# big7segment.net
KiCad netlist of a schematic drawn in EAGLE
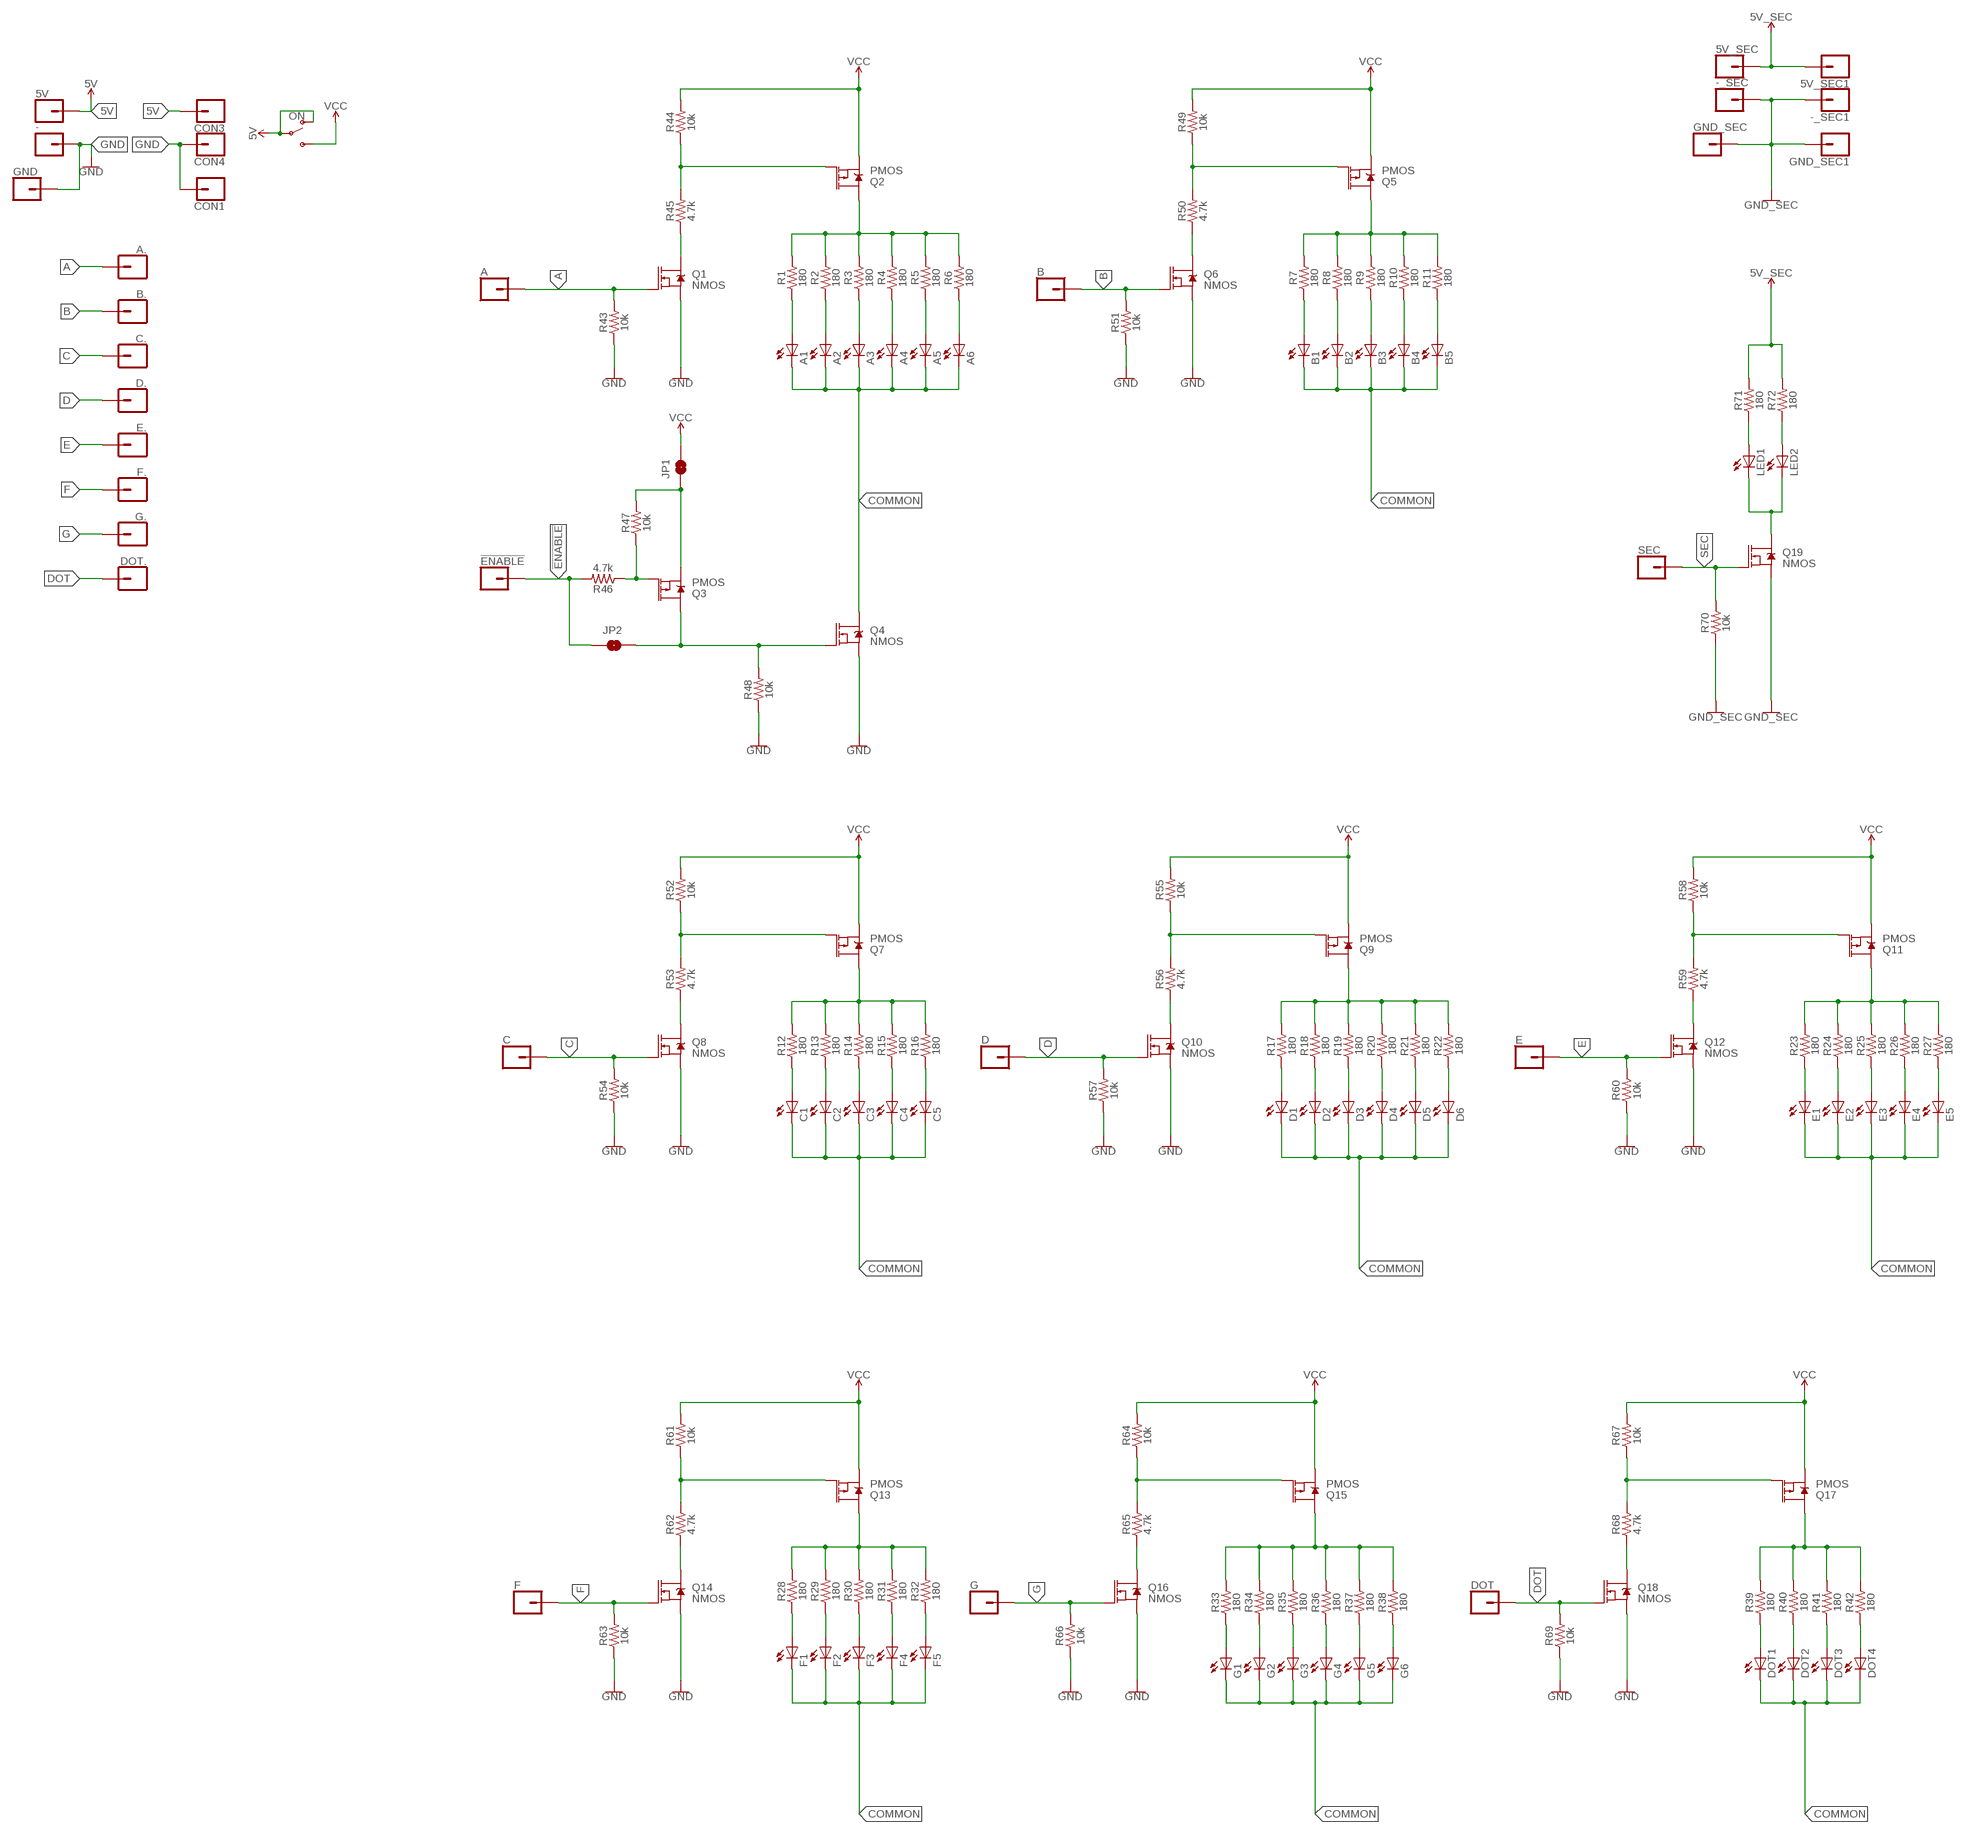
[diagram p0: schematic, sheet 1]

(export (version "E")
  (design (tool "Eeschema 10.0.6"))
  (components
    (comp (ref "!ENABLE!")
      (value "CONN_01OFFSET")
      (footprint "eagle-import:1X01_OFFSET")
      (libsource (lib "eagle-import") (part "CONN_01OFFSET"))
    )
    (comp (ref "-")
      (value "CONN_01OFFSET")
      (footprint "eagle-import:1X01_OFFSET")
      (libsource (lib "eagle-import") (part "CONN_01OFFSET"))
    )
    (comp (ref "-_SEC")
      (value "CONN_01OFFSET")
      (footprint "eagle-import:1X01_OFFSET")
      (libsource (lib "eagle-import") (part "CONN_01OFFSET"))
    )
    (comp (ref "-_SEC1")
      (value "CONN_01OFFSET")
      (footprint "eagle-import:1X01_OFFSET")
      (libsource (lib "eagle-import") (part "CONN_01OFFSET"))
    )
    (comp (ref "5V")
      (value "CONN_01OFFSET")
      (footprint "eagle-import:1X01_OFFSET")
      (libsource (lib "eagle-import") (part "CONN_01OFFSET"))
    )
    (comp (ref "5V_SEC")
      (value "CONN_01OFFSET")
      (footprint "eagle-import:1X01_OFFSET")
      (libsource (lib "eagle-import") (part "CONN_01OFFSET"))
    )
    (comp (ref "5V_SEC1")
      (value "CONN_01OFFSET")
      (footprint "eagle-import:1X01_OFFSET")
      (libsource (lib "eagle-import") (part "CONN_01OFFSET"))
    )
    (comp (ref "A")
      (value "CONN_01OFFSET")
      (footprint "eagle-import:1X01_OFFSET")
      (libsource (lib "eagle-import") (part "CONN_01OFFSET"))
    )
    (comp (ref "A.")
      (value "CONN_01OFFSET")
      (footprint "eagle-import:1X01_OFFSET")
      (libsource (lib "eagle-import") (part "CONN_01OFFSET"))
    )
    (comp (ref "A1")
      (value "LEDSML0805")
      (footprint "eagle-import:SML0805")
      (libsource (lib "eagle-import") (part "LEDSML0805"))
    )
    (comp (ref "A2")
      (value "LEDSML0805")
      (footprint "eagle-import:SML0805")
      (libsource (lib "eagle-import") (part "LEDSML0805"))
    )
    (comp (ref "A3")
      (value "LEDSML0805")
      (footprint "eagle-import:SML0805")
      (libsource (lib "eagle-import") (part "LEDSML0805"))
    )
    (comp (ref "A4")
      (value "LEDSML0805")
      (footprint "eagle-import:SML0805")
      (libsource (lib "eagle-import") (part "LEDSML0805"))
    )
    (comp (ref "A5")
      (value "LEDSML0805")
      (footprint "eagle-import:SML0805")
      (libsource (lib "eagle-import") (part "LEDSML0805"))
    )
    (comp (ref "A6")
      (value "LEDSML0805")
      (footprint "eagle-import:SML0805")
      (libsource (lib "eagle-import") (part "LEDSML0805"))
    )
    (comp (ref "B")
      (value "CONN_01OFFSET")
      (footprint "eagle-import:1X01_OFFSET")
      (libsource (lib "eagle-import") (part "CONN_01OFFSET"))
    )
    (comp (ref "B.")
      (value "CONN_01OFFSET")
      (footprint "eagle-import:1X01_OFFSET")
      (libsource (lib "eagle-import") (part "CONN_01OFFSET"))
    )
    (comp (ref "B1")
      (value "LEDSML0805")
      (footprint "eagle-import:SML0805")
      (libsource (lib "eagle-import") (part "LEDSML0805"))
    )
    (comp (ref "B2")
      (value "LEDSML0805")
      (footprint "eagle-import:SML0805")
      (libsource (lib "eagle-import") (part "LEDSML0805"))
    )
    (comp (ref "B3")
      (value "LEDSML0805")
      (footprint "eagle-import:SML0805")
      (libsource (lib "eagle-import") (part "LEDSML0805"))
    )
    (comp (ref "B4")
      (value "LEDSML0805")
      (footprint "eagle-import:SML0805")
      (libsource (lib "eagle-import") (part "LEDSML0805"))
    )
    (comp (ref "B5")
      (value "LEDSML0805")
      (footprint "eagle-import:SML0805")
      (libsource (lib "eagle-import") (part "LEDSML0805"))
    )
    (comp (ref "C")
      (value "CONN_01OFFSET")
      (footprint "eagle-import:1X01_OFFSET")
      (libsource (lib "eagle-import") (part "CONN_01OFFSET"))
    )
    (comp (ref "C.")
      (value "CONN_01OFFSET")
      (footprint "eagle-import:1X01_OFFSET")
      (libsource (lib "eagle-import") (part "CONN_01OFFSET"))
    )
    (comp (ref "C1")
      (value "LEDSML0805")
      (footprint "eagle-import:SML0805")
      (libsource (lib "eagle-import") (part "LEDSML0805"))
    )
    (comp (ref "C2")
      (value "LEDSML0805")
      (footprint "eagle-import:SML0805")
      (libsource (lib "eagle-import") (part "LEDSML0805"))
    )
    (comp (ref "C3")
      (value "LEDSML0805")
      (footprint "eagle-import:SML0805")
      (libsource (lib "eagle-import") (part "LEDSML0805"))
    )
    (comp (ref "C4")
      (value "LEDSML0805")
      (footprint "eagle-import:SML0805")
      (libsource (lib "eagle-import") (part "LEDSML0805"))
    )
    (comp (ref "C5")
      (value "LEDSML0805")
      (footprint "eagle-import:SML0805")
      (libsource (lib "eagle-import") (part "LEDSML0805"))
    )
    (comp (ref "CON1")
      (value "CONN_01OFFSET")
      (footprint "eagle-import:1X01_OFFSET")
      (libsource (lib "eagle-import") (part "CONN_01OFFSET"))
    )
    (comp (ref "CON3")
      (value "CONN_01OFFSET")
      (footprint "eagle-import:1X01_OFFSET")
      (libsource (lib "eagle-import") (part "CONN_01OFFSET"))
    )
    (comp (ref "CON4")
      (value "CONN_01OFFSET")
      (footprint "eagle-import:1X01_OFFSET")
      (libsource (lib "eagle-import") (part "CONN_01OFFSET"))
    )
    (comp (ref "D")
      (value "CONN_01OFFSET")
      (footprint "eagle-import:1X01_OFFSET")
      (libsource (lib "eagle-import") (part "CONN_01OFFSET"))
    )
    (comp (ref "D.")
      (value "CONN_01OFFSET")
      (footprint "eagle-import:1X01_OFFSET")
      (libsource (lib "eagle-import") (part "CONN_01OFFSET"))
    )
    (comp (ref "D1")
      (value "LEDSML0805")
      (footprint "eagle-import:SML0805")
      (libsource (lib "eagle-import") (part "LEDSML0805"))
    )
    (comp (ref "D2")
      (value "LEDSML0805")
      (footprint "eagle-import:SML0805")
      (libsource (lib "eagle-import") (part "LEDSML0805"))
    )
    (comp (ref "D3")
      (value "LEDSML0805")
      (footprint "eagle-import:SML0805")
      (libsource (lib "eagle-import") (part "LEDSML0805"))
    )
    (comp (ref "D4")
      (value "LEDSML0805")
      (footprint "eagle-import:SML0805")
      (libsource (lib "eagle-import") (part "LEDSML0805"))
    )
    (comp (ref "D5")
      (value "LEDSML0805")
      (footprint "eagle-import:SML0805")
      (libsource (lib "eagle-import") (part "LEDSML0805"))
    )
    (comp (ref "D6")
      (value "LEDSML0805")
      (footprint "eagle-import:SML0805")
      (libsource (lib "eagle-import") (part "LEDSML0805"))
    )
    (comp (ref "DOT")
      (value "CONN_01OFFSET")
      (footprint "eagle-import:1X01_OFFSET")
      (libsource (lib "eagle-import") (part "CONN_01OFFSET"))
    )
    (comp (ref "DOT.")
      (value "CONN_01OFFSET")
      (footprint "eagle-import:1X01_OFFSET")
      (libsource (lib "eagle-import") (part "CONN_01OFFSET"))
    )
    (comp (ref "DOT1")
      (value "LEDSML0805")
      (footprint "eagle-import:SML0805")
      (libsource (lib "eagle-import") (part "LEDSML0805"))
    )
    (comp (ref "DOT2")
      (value "LEDSML0805")
      (footprint "eagle-import:SML0805")
      (libsource (lib "eagle-import") (part "LEDSML0805"))
    )
    (comp (ref "DOT3")
      (value "LEDSML0805")
      (footprint "eagle-import:SML0805")
      (libsource (lib "eagle-import") (part "LEDSML0805"))
    )
    (comp (ref "DOT4")
      (value "LEDSML0805")
      (footprint "eagle-import:SML0805")
      (libsource (lib "eagle-import") (part "LEDSML0805"))
    )
    (comp (ref "E")
      (value "CONN_01OFFSET")
      (footprint "eagle-import:1X01_OFFSET")
      (libsource (lib "eagle-import") (part "CONN_01OFFSET"))
    )
    (comp (ref "E.")
      (value "CONN_01OFFSET")
      (footprint "eagle-import:1X01_OFFSET")
      (libsource (lib "eagle-import") (part "CONN_01OFFSET"))
    )
    (comp (ref "E1")
      (value "LEDSML0805")
      (footprint "eagle-import:SML0805")
      (libsource (lib "eagle-import") (part "LEDSML0805"))
    )
    (comp (ref "E2")
      (value "LEDSML0805")
      (footprint "eagle-import:SML0805")
      (libsource (lib "eagle-import") (part "LEDSML0805"))
    )
    (comp (ref "E3")
      (value "LEDSML0805")
      (footprint "eagle-import:SML0805")
      (libsource (lib "eagle-import") (part "LEDSML0805"))
    )
    (comp (ref "E4")
      (value "LEDSML0805")
      (footprint "eagle-import:SML0805")
      (libsource (lib "eagle-import") (part "LEDSML0805"))
    )
    (comp (ref "E5")
      (value "LEDSML0805")
      (footprint "eagle-import:SML0805")
      (libsource (lib "eagle-import") (part "LEDSML0805"))
    )
    (comp (ref "F")
      (value "CONN_01OFFSET")
      (footprint "eagle-import:1X01_OFFSET")
      (libsource (lib "eagle-import") (part "CONN_01OFFSET"))
    )
    (comp (ref "F.")
      (value "CONN_01OFFSET")
      (footprint "eagle-import:1X01_OFFSET")
      (libsource (lib "eagle-import") (part "CONN_01OFFSET"))
    )
    (comp (ref "F1")
      (value "LEDSML0805")
      (footprint "eagle-import:SML0805")
      (libsource (lib "eagle-import") (part "LEDSML0805"))
    )
    (comp (ref "F2")
      (value "LEDSML0805")
      (footprint "eagle-import:SML0805")
      (libsource (lib "eagle-import") (part "LEDSML0805"))
    )
    (comp (ref "F3")
      (value "LEDSML0805")
      (footprint "eagle-import:SML0805")
      (libsource (lib "eagle-import") (part "LEDSML0805"))
    )
    (comp (ref "F4")
      (value "LEDSML0805")
      (footprint "eagle-import:SML0805")
      (libsource (lib "eagle-import") (part "LEDSML0805"))
    )
    (comp (ref "F5")
      (value "LEDSML0805")
      (footprint "eagle-import:SML0805")
      (libsource (lib "eagle-import") (part "LEDSML0805"))
    )
    (comp (ref "G")
      (value "CONN_01OFFSET")
      (footprint "eagle-import:1X01_OFFSET")
      (libsource (lib "eagle-import") (part "CONN_01OFFSET"))
    )
    (comp (ref "G.")
      (value "CONN_01OFFSET")
      (footprint "eagle-import:1X01_OFFSET")
      (libsource (lib "eagle-import") (part "CONN_01OFFSET"))
    )
    (comp (ref "G1")
      (value "LEDSML0805")
      (footprint "eagle-import:SML0805")
      (libsource (lib "eagle-import") (part "LEDSML0805"))
    )
    (comp (ref "G2")
      (value "LEDSML0805")
      (footprint "eagle-import:SML0805")
      (libsource (lib "eagle-import") (part "LEDSML0805"))
    )
    (comp (ref "G3")
      (value "LEDSML0805")
      (footprint "eagle-import:SML0805")
      (libsource (lib "eagle-import") (part "LEDSML0805"))
    )
    (comp (ref "G4")
      (value "LEDSML0805")
      (footprint "eagle-import:SML0805")
      (libsource (lib "eagle-import") (part "LEDSML0805"))
    )
    (comp (ref "G5")
      (value "LEDSML0805")
      (footprint "eagle-import:SML0805")
      (libsource (lib "eagle-import") (part "LEDSML0805"))
    )
    (comp (ref "G6")
      (value "LEDSML0805")
      (footprint "eagle-import:SML0805")
      (libsource (lib "eagle-import") (part "LEDSML0805"))
    )
    (comp (ref "GND")
      (value "CONN_01OFFSET")
      (footprint "eagle-import:1X01_OFFSET")
      (libsource (lib "eagle-import") (part "CONN_01OFFSET"))
    )
    (comp (ref "GND_SEC")
      (value "CONN_01OFFSET")
      (footprint "eagle-import:1X01_OFFSET")
      (libsource (lib "eagle-import") (part "CONN_01OFFSET"))
    )
    (comp (ref "GND_SEC1")
      (value "CONN_01OFFSET")
      (footprint "eagle-import:1X01_OFFSET")
      (libsource (lib "eagle-import") (part "CONN_01OFFSET"))
    )
    (comp (ref "JP1")
      (value "JUMPER-SMT_2_NC_TRACE_NO-SILK")
      (footprint "eagle-import:SMT-JUMPER_2_NC_TRACE_NO-SILK")
      (libsource (lib "eagle-import") (part "JUMPER-SMT_2_NC_TRACE_NO-SILK"))
    )
    (comp (ref "JP2")
      (value "JUMPER-SMT_2_NO_NO-SILK")
      (footprint "eagle-import:SMT-JUMPER_2_NO_NO-SILK")
      (libsource (lib "eagle-import") (part "JUMPER-SMT_2_NO_NO-SILK"))
    )
    (comp (ref "LED1")
      (value "LED5MM")
      (footprint "eagle-import:LED5MM")
      (libsource (lib "eagle-import") (part "LED5MM"))
    )
    (comp (ref "LED2")
      (value "LED5MM")
      (footprint "eagle-import:LED5MM")
      (libsource (lib "eagle-import") (part "LED5MM"))
    )
    (comp (ref "ON")
      (value "SWITCH-SPDT-PTH-11.6X4.0MM")
      (footprint "eagle-import:SWITCH_SPDT_PTH_11.6X4.0MM")
      (libsource (lib "eagle-import") (part "SWITCH-SPDT-PTH-11.6X4.0MM"))
    )
    (comp (ref "Q1")
      (value "NMOS")
      (footprint "eagle-import:SOT23-3")
      (libsource (lib "eagle-import") (part "MOSFET-NCH-AO3404A"))
    )
    (comp (ref "Q2")
      (value "PMOS")
      (footprint "eagle-import:SOT23-3")
      (libsource (lib "eagle-import") (part "MOSFET_PCH-DMG2307L"))
    )
    (comp (ref "Q3")
      (value "PMOS")
      (footprint "eagle-import:SOT23-3")
      (libsource (lib "eagle-import") (part "MOSFET_PCH-DMG2307L"))
    )
    (comp (ref "Q4")
      (value "NMOS")
      (footprint "eagle-import:SOT23-3")
      (libsource (lib "eagle-import") (part "MOSFET-NCH-AO3404A"))
    )
    (comp (ref "Q5")
      (value "PMOS")
      (footprint "eagle-import:SOT23-3")
      (libsource (lib "eagle-import") (part "MOSFET_PCH-DMG2307L"))
    )
    (comp (ref "Q6")
      (value "NMOS")
      (footprint "eagle-import:SOT23-3")
      (libsource (lib "eagle-import") (part "MOSFET-NCH-AO3404A"))
    )
    (comp (ref "Q7")
      (value "PMOS")
      (footprint "eagle-import:SOT23-3")
      (libsource (lib "eagle-import") (part "MOSFET_PCH-DMG2307L"))
    )
    (comp (ref "Q8")
      (value "NMOS")
      (footprint "eagle-import:SOT23-3")
      (libsource (lib "eagle-import") (part "MOSFET-NCH-AO3404A"))
    )
    (comp (ref "Q9")
      (value "PMOS")
      (footprint "eagle-import:SOT23-3")
      (libsource (lib "eagle-import") (part "MOSFET_PCH-DMG2307L"))
    )
    (comp (ref "Q10")
      (value "NMOS")
      (footprint "eagle-import:SOT23-3")
      (libsource (lib "eagle-import") (part "MOSFET-NCH-AO3404A"))
    )
    (comp (ref "Q11")
      (value "PMOS")
      (footprint "eagle-import:SOT23-3")
      (libsource (lib "eagle-import") (part "MOSFET_PCH-DMG2307L"))
    )
    (comp (ref "Q12")
      (value "NMOS")
      (footprint "eagle-import:SOT23-3")
      (libsource (lib "eagle-import") (part "MOSFET-NCH-AO3404A"))
    )
    (comp (ref "Q13")
      (value "PMOS")
      (footprint "eagle-import:SOT23-3")
      (libsource (lib "eagle-import") (part "MOSFET_PCH-DMG2307L"))
    )
    (comp (ref "Q14")
      (value "NMOS")
      (footprint "eagle-import:SOT23-3")
      (libsource (lib "eagle-import") (part "MOSFET-NCH-AO3404A"))
    )
    (comp (ref "Q15")
      (value "PMOS")
      (footprint "eagle-import:SOT23-3")
      (libsource (lib "eagle-import") (part "MOSFET_PCH-DMG2307L"))
    )
    (comp (ref "Q16")
      (value "NMOS")
      (footprint "eagle-import:SOT23-3")
      (libsource (lib "eagle-import") (part "MOSFET-NCH-AO3404A"))
    )
    (comp (ref "Q17")
      (value "PMOS")
      (footprint "eagle-import:SOT23-3")
      (libsource (lib "eagle-import") (part "MOSFET_PCH-DMG2307L"))
    )
    (comp (ref "Q18")
      (value "NMOS")
      (footprint "eagle-import:SOT23-3")
      (libsource (lib "eagle-import") (part "MOSFET-NCH-AO3404A"))
    )
    (comp (ref "Q19")
      (value "NMOS")
      (footprint "eagle-import:SOT23-3")
      (libsource (lib "eagle-import") (part "MOSFET-NCH-AO3404A"))
    )
    (comp (ref "R1")
      (value "180")
      (footprint "eagle-import:0805")
      (libsource (lib "eagle-import") (part "0.3OHM-0805-1/8W-1%"))
    )
    (comp (ref "R2")
      (value "180")
      (footprint "eagle-import:0805")
      (libsource (lib "eagle-import") (part "0.3OHM-0805-1/8W-1%"))
    )
    (comp (ref "R3")
      (value "180")
      (footprint "eagle-import:0805")
      (libsource (lib "eagle-import") (part "0.3OHM-0805-1/8W-1%"))
    )
    (comp (ref "R4")
      (value "180")
      (footprint "eagle-import:0805")
      (libsource (lib "eagle-import") (part "0.3OHM-0805-1/8W-1%"))
    )
    (comp (ref "R5")
      (value "180")
      (footprint "eagle-import:0805")
      (libsource (lib "eagle-import") (part "0.3OHM-0805-1/8W-1%"))
    )
    (comp (ref "R6")
      (value "180")
      (footprint "eagle-import:0805")
      (libsource (lib "eagle-import") (part "0.3OHM-0805-1/8W-1%"))
    )
    (comp (ref "R7")
      (value "180")
      (footprint "eagle-import:0805")
      (libsource (lib "eagle-import") (part "0.3OHM-0805-1/8W-1%"))
    )
    (comp (ref "R8")
      (value "180")
      (footprint "eagle-import:0805")
      (libsource (lib "eagle-import") (part "0.3OHM-0805-1/8W-1%"))
    )
    (comp (ref "R9")
      (value "180")
      (footprint "eagle-import:0805")
      (libsource (lib "eagle-import") (part "0.3OHM-0805-1/8W-1%"))
    )
    (comp (ref "R10")
      (value "180")
      (footprint "eagle-import:0805")
      (libsource (lib "eagle-import") (part "0.3OHM-0805-1/8W-1%"))
    )
    (comp (ref "R11")
      (value "180")
      (footprint "eagle-import:0805")
      (libsource (lib "eagle-import") (part "0.3OHM-0805-1/8W-1%"))
    )
    (comp (ref "R12")
      (value "180")
      (footprint "eagle-import:0805")
      (libsource (lib "eagle-import") (part "0.3OHM-0805-1/8W-1%"))
    )
    (comp (ref "R13")
      (value "180")
      (footprint "eagle-import:0805")
      (libsource (lib "eagle-import") (part "0.3OHM-0805-1/8W-1%"))
    )
    (comp (ref "R14")
      (value "180")
      (footprint "eagle-import:0805")
      (libsource (lib "eagle-import") (part "0.3OHM-0805-1/8W-1%"))
    )
    (comp (ref "R15")
      (value "180")
      (footprint "eagle-import:0805")
      (libsource (lib "eagle-import") (part "0.3OHM-0805-1/8W-1%"))
    )
    (comp (ref "R16")
      (value "180")
      (footprint "eagle-import:0805")
      (libsource (lib "eagle-import") (part "0.3OHM-0805-1/8W-1%"))
    )
    (comp (ref "R17")
      (value "180")
      (footprint "eagle-import:0805")
      (libsource (lib "eagle-import") (part "0.3OHM-0805-1/8W-1%"))
    )
    (comp (ref "R18")
      (value "180")
      (footprint "eagle-import:0805")
      (libsource (lib "eagle-import") (part "0.3OHM-0805-1/8W-1%"))
    )
    (comp (ref "R19")
      (value "180")
      (footprint "eagle-import:0805")
      (libsource (lib "eagle-import") (part "0.3OHM-0805-1/8W-1%"))
    )
    (comp (ref "R20")
      (value "180")
      (footprint "eagle-import:0805")
      (libsource (lib "eagle-import") (part "0.3OHM-0805-1/8W-1%"))
    )
    (comp (ref "R21")
      (value "180")
      (footprint "eagle-import:0805")
      (libsource (lib "eagle-import") (part "0.3OHM-0805-1/8W-1%"))
    )
    (comp (ref "R22")
      (value "180")
      (footprint "eagle-import:0805")
      (libsource (lib "eagle-import") (part "0.3OHM-0805-1/8W-1%"))
    )
    (comp (ref "R23")
      (value "180")
      (footprint "eagle-import:0805")
      (libsource (lib "eagle-import") (part "0.3OHM-0805-1/8W-1%"))
    )
    (comp (ref "R24")
      (value "180")
      (footprint "eagle-import:0805")
      (libsource (lib "eagle-import") (part "0.3OHM-0805-1/8W-1%"))
    )
    (comp (ref "R25")
      (value "180")
      (footprint "eagle-import:0805")
      (libsource (lib "eagle-import") (part "0.3OHM-0805-1/8W-1%"))
    )
    (comp (ref "R26")
      (value "180")
      (footprint "eagle-import:0805")
      (libsource (lib "eagle-import") (part "0.3OHM-0805-1/8W-1%"))
    )
    (comp (ref "R27")
      (value "180")
      (footprint "eagle-import:0805")
      (libsource (lib "eagle-import") (part "0.3OHM-0805-1/8W-1%"))
    )
    (comp (ref "R28")
      (value "180")
      (footprint "eagle-import:0805")
      (libsource (lib "eagle-import") (part "0.3OHM-0805-1/8W-1%"))
    )
    (comp (ref "R29")
      (value "180")
      (footprint "eagle-import:0805")
      (libsource (lib "eagle-import") (part "0.3OHM-0805-1/8W-1%"))
    )
    (comp (ref "R30")
      (value "180")
      (footprint "eagle-import:0805")
      (libsource (lib "eagle-import") (part "0.3OHM-0805-1/8W-1%"))
    )
    (comp (ref "R31")
      (value "180")
      (footprint "eagle-import:0805")
      (libsource (lib "eagle-import") (part "0.3OHM-0805-1/8W-1%"))
    )
    (comp (ref "R32")
      (value "180")
      (footprint "eagle-import:0805")
      (libsource (lib "eagle-import") (part "0.3OHM-0805-1/8W-1%"))
    )
    (comp (ref "R33")
      (value "180")
      (footprint "eagle-import:0805")
      (libsource (lib "eagle-import") (part "0.3OHM-0805-1/8W-1%"))
    )
    (comp (ref "R34")
      (value "180")
      (footprint "eagle-import:0805")
      (libsource (lib "eagle-import") (part "0.3OHM-0805-1/8W-1%"))
    )
    (comp (ref "R35")
      (value "180")
      (footprint "eagle-import:0805")
      (libsource (lib "eagle-import") (part "0.3OHM-0805-1/8W-1%"))
    )
    (comp (ref "R36")
      (value "180")
      (footprint "eagle-import:0805")
      (libsource (lib "eagle-import") (part "0.3OHM-0805-1/8W-1%"))
    )
    (comp (ref "R37")
      (value "180")
      (footprint "eagle-import:0805")
      (libsource (lib "eagle-import") (part "0.3OHM-0805-1/8W-1%"))
    )
    (comp (ref "R38")
      (value "180")
      (footprint "eagle-import:0805")
      (libsource (lib "eagle-import") (part "0.3OHM-0805-1/8W-1%"))
    )
    (comp (ref "R39")
      (value "180")
      (footprint "eagle-import:0805")
      (libsource (lib "eagle-import") (part "0.3OHM-0805-1/8W-1%"))
    )
    (comp (ref "R40")
      (value "180")
      (footprint "eagle-import:0805")
      (libsource (lib "eagle-import") (part "0.3OHM-0805-1/8W-1%"))
    )
    (comp (ref "R41")
      (value "180")
      (footprint "eagle-import:0805")
      (libsource (lib "eagle-import") (part "0.3OHM-0805-1/8W-1%"))
    )
    (comp (ref "R42")
      (value "180")
      (footprint "eagle-import:0805")
      (libsource (lib "eagle-import") (part "0.3OHM-0805-1/8W-1%"))
    )
    (comp (ref "R43")
      (value "10k")
      (footprint "eagle-import:0805")
      (libsource (lib "eagle-import") (part "0.3OHM-0805-1/8W-1%"))
    )
    (comp (ref "R44")
      (value "10k")
      (footprint "eagle-import:0805")
      (libsource (lib "eagle-import") (part "0.3OHM-0805-1/8W-1%"))
    )
    (comp (ref "R45")
      (value "4.7k")
      (footprint "eagle-import:0805")
      (libsource (lib "eagle-import") (part "0.3OHM-0805-1/8W-1%"))
    )
    (comp (ref "R46")
      (value "4.7k")
      (footprint "eagle-import:0805")
      (libsource (lib "eagle-import") (part "0.3OHM-0805-1/8W-1%"))
    )
    (comp (ref "R47")
      (value "10k")
      (footprint "eagle-import:0805")
      (libsource (lib "eagle-import") (part "0.3OHM-0805-1/8W-1%"))
    )
    (comp (ref "R48")
      (value "10k")
      (footprint "eagle-import:0805")
      (libsource (lib "eagle-import") (part "0.3OHM-0805-1/8W-1%"))
    )
    (comp (ref "R49")
      (value "10k")
      (footprint "eagle-import:0805")
      (libsource (lib "eagle-import") (part "0.3OHM-0805-1/8W-1%"))
    )
    (comp (ref "R50")
      (value "4.7k")
      (footprint "eagle-import:0805")
      (libsource (lib "eagle-import") (part "0.3OHM-0805-1/8W-1%"))
    )
    (comp (ref "R51")
      (value "10k")
      (footprint "eagle-import:0805")
      (libsource (lib "eagle-import") (part "0.3OHM-0805-1/8W-1%"))
    )
    (comp (ref "R52")
      (value "10k")
      (footprint "eagle-import:0805")
      (libsource (lib "eagle-import") (part "0.3OHM-0805-1/8W-1%"))
    )
    (comp (ref "R53")
      (value "4.7k")
      (footprint "eagle-import:0805")
      (libsource (lib "eagle-import") (part "0.3OHM-0805-1/8W-1%"))
    )
    (comp (ref "R54")
      (value "10k")
      (footprint "eagle-import:0805")
      (libsource (lib "eagle-import") (part "0.3OHM-0805-1/8W-1%"))
    )
    (comp (ref "R55")
      (value "10k")
      (footprint "eagle-import:0805")
      (libsource (lib "eagle-import") (part "0.3OHM-0805-1/8W-1%"))
    )
    (comp (ref "R56")
      (value "4.7k")
      (footprint "eagle-import:0805")
      (libsource (lib "eagle-import") (part "0.3OHM-0805-1/8W-1%"))
    )
    (comp (ref "R57")
      (value "10k")
      (footprint "eagle-import:0805")
      (libsource (lib "eagle-import") (part "0.3OHM-0805-1/8W-1%"))
    )
    (comp (ref "R58")
      (value "10k")
      (footprint "eagle-import:0805")
      (libsource (lib "eagle-import") (part "0.3OHM-0805-1/8W-1%"))
    )
    (comp (ref "R59")
      (value "4.7k")
      (footprint "eagle-import:0805")
      (libsource (lib "eagle-import") (part "0.3OHM-0805-1/8W-1%"))
    )
    (comp (ref "R60")
      (value "10k")
      (footprint "eagle-import:0805")
      (libsource (lib "eagle-import") (part "0.3OHM-0805-1/8W-1%"))
    )
    (comp (ref "R61")
      (value "10k")
      (footprint "eagle-import:0805")
      (libsource (lib "eagle-import") (part "0.3OHM-0805-1/8W-1%"))
    )
    (comp (ref "R62")
      (value "4.7k")
      (footprint "eagle-import:0805")
      (libsource (lib "eagle-import") (part "0.3OHM-0805-1/8W-1%"))
    )
    (comp (ref "R63")
      (value "10k")
      (footprint "eagle-import:0805")
      (libsource (lib "eagle-import") (part "0.3OHM-0805-1/8W-1%"))
    )
    (comp (ref "R64")
      (value "10k")
      (footprint "eagle-import:0805")
      (libsource (lib "eagle-import") (part "0.3OHM-0805-1/8W-1%"))
    )
    (comp (ref "R65")
      (value "4.7k")
      (footprint "eagle-import:0805")
      (libsource (lib "eagle-import") (part "0.3OHM-0805-1/8W-1%"))
    )
    (comp (ref "R66")
      (value "10k")
      (footprint "eagle-import:0805")
      (libsource (lib "eagle-import") (part "0.3OHM-0805-1/8W-1%"))
    )
    (comp (ref "R67")
      (value "10k")
      (footprint "eagle-import:0805")
      (libsource (lib "eagle-import") (part "0.3OHM-0805-1/8W-1%"))
    )
    (comp (ref "R68")
      (value "4.7k")
      (footprint "eagle-import:0805")
      (libsource (lib "eagle-import") (part "0.3OHM-0805-1/8W-1%"))
    )
    (comp (ref "R69")
      (value "10k")
      (footprint "eagle-import:0805")
      (libsource (lib "eagle-import") (part "0.3OHM-0805-1/8W-1%"))
    )
    (comp (ref "R70")
      (value "10k")
      (footprint "eagle-import:0805")
      (libsource (lib "eagle-import") (part "0.3OHM-0805-1/8W-1%"))
    )
    (comp (ref "R71")
      (value "180")
      (footprint "eagle-import:0805")
      (libsource (lib "eagle-import") (part "0.3OHM-0805-1/8W-1%"))
    )
    (comp (ref "R72")
      (value "180")
      (footprint "eagle-import:0805")
      (libsource (lib "eagle-import") (part "0.3OHM-0805-1/8W-1%"))
    )
    (comp (ref "SEC")
      (value "CONN_01OFFSET")
      (footprint "eagle-import:1X01_OFFSET")
      (libsource (lib "eagle-import") (part "CONN_01OFFSET"))
    )
  )
  (nets
    (net (code "1") (name "/~{ENABLE}") (class "Default")
      (node (ref "!ENABLE!") (pin "1") (pinfunction "1_1") (pintype "passive"))
      (node (ref "JP2") (pin "1") (pinfunction "1_1") (pintype "passive"))
      (node (ref "R46") (pin "2") (pinfunction "2_2") (pintype "passive"))
    )
    (net (code "2") (name "5V") (class "Default")
      (node (ref "5V") (pin "1") (pinfunction "1_1") (pintype "passive"))
      (node (ref "CON3") (pin "1") (pinfunction "1_1") (pintype "passive"))
      (node (ref "ON") (pin "1") (pinfunction "O_1") (pintype "passive"))
      (node (ref "ON") (pin "2") (pinfunction "P_2") (pintype "passive"))
    )
    (net (code "3") (name "5V_SEC") (class "Default")
      (node (ref "5V_SEC") (pin "1") (pinfunction "1_1") (pintype "passive"))
      (node (ref "5V_SEC1") (pin "1") (pinfunction "1_1") (pintype "passive"))
      (node (ref "R71") (pin "2") (pinfunction "2_2") (pintype "passive"))
      (node (ref "R72") (pin "2") (pinfunction "2_2") (pintype "passive"))
    )
    (net (code "4") (name "A") (class "Default")
      (node (ref "A") (pin "1") (pinfunction "1_1") (pintype "passive"))
      (node (ref "A.") (pin "1") (pinfunction "1_1") (pintype "passive"))
      (node (ref "Q1") (pin "1") (pinfunction "G_1") (pintype "bidirectional"))
      (node (ref "R43") (pin "2") (pinfunction "2_2") (pintype "passive"))
    )
    (net (code "5") (name "B") (class "Default")
      (node (ref "B") (pin "1") (pinfunction "1_1") (pintype "passive"))
      (node (ref "B.") (pin "1") (pinfunction "1_1") (pintype "passive"))
      (node (ref "Q6") (pin "1") (pinfunction "G_1") (pintype "bidirectional"))
      (node (ref "R51") (pin "2") (pinfunction "2_2") (pintype "passive"))
    )
    (net (code "6") (name "C") (class "Default")
      (node (ref "C") (pin "1") (pinfunction "1_1") (pintype "passive"))
      (node (ref "C.") (pin "1") (pinfunction "1_1") (pintype "passive"))
      (node (ref "Q8") (pin "1") (pinfunction "G_1") (pintype "bidirectional"))
      (node (ref "R54") (pin "2") (pinfunction "2_2") (pintype "passive"))
    )
    (net (code "7") (name "COMMON") (class "Default")
      (node (ref "A1") (pin "C") (pinfunction "C_C") (pintype "passive"))
      (node (ref "A2") (pin "C") (pinfunction "C_C") (pintype "passive"))
      (node (ref "A3") (pin "C") (pinfunction "C_C") (pintype "passive"))
      (node (ref "A4") (pin "C") (pinfunction "C_C") (pintype "passive"))
      (node (ref "A5") (pin "C") (pinfunction "C_C") (pintype "passive"))
      (node (ref "A6") (pin "C") (pinfunction "C_C") (pintype "passive"))
      (node (ref "B1") (pin "C") (pinfunction "C_C") (pintype "passive"))
      (node (ref "B2") (pin "C") (pinfunction "C_C") (pintype "passive"))
      (node (ref "B3") (pin "C") (pinfunction "C_C") (pintype "passive"))
      (node (ref "B4") (pin "C") (pinfunction "C_C") (pintype "passive"))
      (node (ref "B5") (pin "C") (pinfunction "C_C") (pintype "passive"))
      (node (ref "C1") (pin "C") (pinfunction "C_C") (pintype "passive"))
      (node (ref "C2") (pin "C") (pinfunction "C_C") (pintype "passive"))
      (node (ref "C3") (pin "C") (pinfunction "C_C") (pintype "passive"))
      (node (ref "C4") (pin "C") (pinfunction "C_C") (pintype "passive"))
      (node (ref "C5") (pin "C") (pinfunction "C_C") (pintype "passive"))
      (node (ref "D1") (pin "C") (pinfunction "C_C") (pintype "passive"))
      (node (ref "D2") (pin "C") (pinfunction "C_C") (pintype "passive"))
      (node (ref "D3") (pin "C") (pinfunction "C_C") (pintype "passive"))
      (node (ref "D4") (pin "C") (pinfunction "C_C") (pintype "passive"))
      (node (ref "D5") (pin "C") (pinfunction "C_C") (pintype "passive"))
      (node (ref "D6") (pin "C") (pinfunction "C_C") (pintype "passive"))
      (node (ref "DOT1") (pin "C") (pinfunction "C_C") (pintype "passive"))
      (node (ref "DOT2") (pin "C") (pinfunction "C_C") (pintype "passive"))
      (node (ref "DOT3") (pin "C") (pinfunction "C_C") (pintype "passive"))
      (node (ref "DOT4") (pin "C") (pinfunction "C_C") (pintype "passive"))
      (node (ref "E1") (pin "C") (pinfunction "C_C") (pintype "passive"))
      (node (ref "E2") (pin "C") (pinfunction "C_C") (pintype "passive"))
      (node (ref "E3") (pin "C") (pinfunction "C_C") (pintype "passive"))
      (node (ref "E4") (pin "C") (pinfunction "C_C") (pintype "passive"))
      (node (ref "E5") (pin "C") (pinfunction "C_C") (pintype "passive"))
      (node (ref "F1") (pin "C") (pinfunction "C_C") (pintype "passive"))
      (node (ref "F2") (pin "C") (pinfunction "C_C") (pintype "passive"))
      (node (ref "F3") (pin "C") (pinfunction "C_C") (pintype "passive"))
      (node (ref "F4") (pin "C") (pinfunction "C_C") (pintype "passive"))
      (node (ref "F5") (pin "C") (pinfunction "C_C") (pintype "passive"))
      (node (ref "G1") (pin "C") (pinfunction "C_C") (pintype "passive"))
      (node (ref "G2") (pin "C") (pinfunction "C_C") (pintype "passive"))
      (node (ref "G3") (pin "C") (pinfunction "C_C") (pintype "passive"))
      (node (ref "G4") (pin "C") (pinfunction "C_C") (pintype "passive"))
      (node (ref "G5") (pin "C") (pinfunction "C_C") (pintype "passive"))
      (node (ref "G6") (pin "C") (pinfunction "C_C") (pintype "passive"))
      (node (ref "Q4") (pin "3") (pinfunction "D_3") (pintype "bidirectional"))
    )
    (net (code "8") (name "D") (class "Default")
      (node (ref "D") (pin "1") (pinfunction "1_1") (pintype "passive"))
      (node (ref "D.") (pin "1") (pinfunction "1_1") (pintype "passive"))
      (node (ref "Q10") (pin "1") (pinfunction "G_1") (pintype "bidirectional"))
      (node (ref "R57") (pin "2") (pinfunction "2_2") (pintype "passive"))
    )
    (net (code "9") (name "DOT") (class "Default")
      (node (ref "DOT") (pin "1") (pinfunction "1_1") (pintype "passive"))
      (node (ref "DOT.") (pin "1") (pinfunction "1_1") (pintype "passive"))
      (node (ref "Q18") (pin "1") (pinfunction "G_1") (pintype "bidirectional"))
      (node (ref "R69") (pin "2") (pinfunction "2_2") (pintype "passive"))
    )
    (net (code "10") (name "E") (class "Default")
      (node (ref "E") (pin "1") (pinfunction "1_1") (pintype "passive"))
      (node (ref "E.") (pin "1") (pinfunction "1_1") (pintype "passive"))
      (node (ref "Q12") (pin "1") (pinfunction "G_1") (pintype "bidirectional"))
      (node (ref "R60") (pin "2") (pinfunction "2_2") (pintype "passive"))
    )
    (net (code "11") (name "F") (class "Default")
      (node (ref "F") (pin "1") (pinfunction "1_1") (pintype "passive"))
      (node (ref "F.") (pin "1") (pinfunction "1_1") (pintype "passive"))
      (node (ref "Q14") (pin "1") (pinfunction "G_1") (pintype "bidirectional"))
      (node (ref "R63") (pin "2") (pinfunction "2_2") (pintype "passive"))
    )
    (net (code "12") (name "G") (class "Default")
      (node (ref "G") (pin "1") (pinfunction "1_1") (pintype "passive"))
      (node (ref "G.") (pin "1") (pinfunction "1_1") (pintype "passive"))
      (node (ref "Q16") (pin "1") (pinfunction "G_1") (pintype "bidirectional"))
      (node (ref "R66") (pin "2") (pinfunction "2_2") (pintype "passive"))
    )
    (net (code "13") (name "GND") (class "Default")
      (node (ref "-") (pin "1") (pinfunction "1_1") (pintype "passive"))
      (node (ref "CON1") (pin "1") (pinfunction "1_1") (pintype "passive"))
      (node (ref "CON4") (pin "1") (pinfunction "1_1") (pintype "passive"))
      (node (ref "GND") (pin "1") (pinfunction "1_1") (pintype "passive"))
      (node (ref "Q1") (pin "2") (pinfunction "S_2") (pintype "bidirectional"))
      (node (ref "Q10") (pin "2") (pinfunction "S_2") (pintype "bidirectional"))
      (node (ref "Q12") (pin "2") (pinfunction "S_2") (pintype "bidirectional"))
      (node (ref "Q14") (pin "2") (pinfunction "S_2") (pintype "bidirectional"))
      (node (ref "Q16") (pin "2") (pinfunction "S_2") (pintype "bidirectional"))
      (node (ref "Q18") (pin "2") (pinfunction "S_2") (pintype "bidirectional"))
      (node (ref "Q4") (pin "2") (pinfunction "S_2") (pintype "bidirectional"))
      (node (ref "Q6") (pin "2") (pinfunction "S_2") (pintype "bidirectional"))
      (node (ref "Q8") (pin "2") (pinfunction "S_2") (pintype "bidirectional"))
      (node (ref "R43") (pin "1") (pinfunction "1_1") (pintype "passive"))
      (node (ref "R48") (pin "1") (pinfunction "1_1") (pintype "passive"))
      (node (ref "R51") (pin "1") (pinfunction "1_1") (pintype "passive"))
      (node (ref "R54") (pin "1") (pinfunction "1_1") (pintype "passive"))
      (node (ref "R57") (pin "1") (pinfunction "1_1") (pintype "passive"))
      (node (ref "R60") (pin "1") (pinfunction "1_1") (pintype "passive"))
      (node (ref "R63") (pin "1") (pinfunction "1_1") (pintype "passive"))
      (node (ref "R66") (pin "1") (pinfunction "1_1") (pintype "passive"))
      (node (ref "R69") (pin "1") (pinfunction "1_1") (pintype "passive"))
    )
    (net (code "14") (name "GND_SEC") (class "Default")
      (node (ref "-_SEC") (pin "1") (pinfunction "1_1") (pintype "passive"))
      (node (ref "-_SEC1") (pin "1") (pinfunction "1_1") (pintype "passive"))
      (node (ref "GND_SEC") (pin "1") (pinfunction "1_1") (pintype "passive"))
      (node (ref "GND_SEC1") (pin "1") (pinfunction "1_1") (pintype "passive"))
      (node (ref "Q19") (pin "2") (pinfunction "S_2") (pintype "bidirectional"))
      (node (ref "R70") (pin "1") (pinfunction "1_1") (pintype "passive"))
    )
    (net (code "15") (name "Net-(A1-PadA)") (class "Default")
      (node (ref "A1") (pin "A") (pinfunction "A_A") (pintype "passive"))
      (node (ref "R1") (pin "1") (pinfunction "1_1") (pintype "passive"))
    )
    (net (code "16") (name "Net-(A2-PadA)") (class "Default")
      (node (ref "A2") (pin "A") (pinfunction "A_A") (pintype "passive"))
      (node (ref "R2") (pin "1") (pinfunction "1_1") (pintype "passive"))
    )
    (net (code "17") (name "Net-(A3-PadA)") (class "Default")
      (node (ref "A3") (pin "A") (pinfunction "A_A") (pintype "passive"))
      (node (ref "R3") (pin "1") (pinfunction "1_1") (pintype "passive"))
    )
    (net (code "18") (name "Net-(A4-PadA)") (class "Default")
      (node (ref "A4") (pin "A") (pinfunction "A_A") (pintype "passive"))
      (node (ref "R4") (pin "1") (pinfunction "1_1") (pintype "passive"))
    )
    (net (code "19") (name "Net-(A5-PadA)") (class "Default")
      (node (ref "A5") (pin "A") (pinfunction "A_A") (pintype "passive"))
      (node (ref "R5") (pin "1") (pinfunction "1_1") (pintype "passive"))
    )
    (net (code "20") (name "Net-(A6-PadA)") (class "Default")
      (node (ref "A6") (pin "A") (pinfunction "A_A") (pintype "passive"))
      (node (ref "R6") (pin "1") (pinfunction "1_1") (pintype "passive"))
    )
    (net (code "21") (name "Net-(B1-PadA)") (class "Default")
      (node (ref "B1") (pin "A") (pinfunction "A_A") (pintype "passive"))
      (node (ref "R7") (pin "1") (pinfunction "1_1") (pintype "passive"))
    )
    (net (code "22") (name "Net-(B2-PadA)") (class "Default")
      (node (ref "B2") (pin "A") (pinfunction "A_A") (pintype "passive"))
      (node (ref "R8") (pin "1") (pinfunction "1_1") (pintype "passive"))
    )
    (net (code "23") (name "Net-(B3-PadA)") (class "Default")
      (node (ref "B3") (pin "A") (pinfunction "A_A") (pintype "passive"))
      (node (ref "R9") (pin "1") (pinfunction "1_1") (pintype "passive"))
    )
    (net (code "24") (name "Net-(B4-PadA)") (class "Default")
      (node (ref "B4") (pin "A") (pinfunction "A_A") (pintype "passive"))
      (node (ref "R10") (pin "1") (pinfunction "1_1") (pintype "passive"))
    )
    (net (code "25") (name "Net-(B5-PadA)") (class "Default")
      (node (ref "B5") (pin "A") (pinfunction "A_A") (pintype "passive"))
      (node (ref "R11") (pin "1") (pinfunction "1_1") (pintype "passive"))
    )
    (net (code "26") (name "Net-(C1-PadA)") (class "Default")
      (node (ref "C1") (pin "A") (pinfunction "A_A") (pintype "passive"))
      (node (ref "R12") (pin "1") (pinfunction "1_1") (pintype "passive"))
    )
    (net (code "27") (name "Net-(C2-PadA)") (class "Default")
      (node (ref "C2") (pin "A") (pinfunction "A_A") (pintype "passive"))
      (node (ref "R13") (pin "1") (pinfunction "1_1") (pintype "passive"))
    )
    (net (code "28") (name "Net-(C3-PadA)") (class "Default")
      (node (ref "C3") (pin "A") (pinfunction "A_A") (pintype "passive"))
      (node (ref "R14") (pin "1") (pinfunction "1_1") (pintype "passive"))
    )
    (net (code "29") (name "Net-(C4-PadA)") (class "Default")
      (node (ref "C4") (pin "A") (pinfunction "A_A") (pintype "passive"))
      (node (ref "R15") (pin "1") (pinfunction "1_1") (pintype "passive"))
    )
    (net (code "30") (name "Net-(C5-PadA)") (class "Default")
      (node (ref "C5") (pin "A") (pinfunction "A_A") (pintype "passive"))
      (node (ref "R16") (pin "1") (pinfunction "1_1") (pintype "passive"))
    )
    (net (code "31") (name "Net-(D1-PadA)") (class "Default")
      (node (ref "D1") (pin "A") (pinfunction "A_A") (pintype "passive"))
      (node (ref "R17") (pin "1") (pinfunction "1_1") (pintype "passive"))
    )
    (net (code "32") (name "Net-(D2-PadA)") (class "Default")
      (node (ref "D2") (pin "A") (pinfunction "A_A") (pintype "passive"))
      (node (ref "R18") (pin "1") (pinfunction "1_1") (pintype "passive"))
    )
    (net (code "33") (name "Net-(D3-PadA)") (class "Default")
      (node (ref "D3") (pin "A") (pinfunction "A_A") (pintype "passive"))
      (node (ref "R19") (pin "1") (pinfunction "1_1") (pintype "passive"))
    )
    (net (code "34") (name "Net-(D4-PadA)") (class "Default")
      (node (ref "D4") (pin "A") (pinfunction "A_A") (pintype "passive"))
      (node (ref "R20") (pin "1") (pinfunction "1_1") (pintype "passive"))
    )
    (net (code "35") (name "Net-(D5-PadA)") (class "Default")
      (node (ref "D5") (pin "A") (pinfunction "A_A") (pintype "passive"))
      (node (ref "R21") (pin "1") (pinfunction "1_1") (pintype "passive"))
    )
    (net (code "36") (name "Net-(D6-PadA)") (class "Default")
      (node (ref "D6") (pin "A") (pinfunction "A_A") (pintype "passive"))
      (node (ref "R22") (pin "1") (pinfunction "1_1") (pintype "passive"))
    )
    (net (code "37") (name "Net-(DOT1-PadA)") (class "Default")
      (node (ref "DOT1") (pin "A") (pinfunction "A_A") (pintype "passive"))
      (node (ref "R39") (pin "1") (pinfunction "1_1") (pintype "passive"))
    )
    (net (code "38") (name "Net-(DOT2-PadA)") (class "Default")
      (node (ref "DOT2") (pin "A") (pinfunction "A_A") (pintype "passive"))
      (node (ref "R40") (pin "1") (pinfunction "1_1") (pintype "passive"))
    )
    (net (code "39") (name "Net-(DOT3-PadA)") (class "Default")
      (node (ref "DOT3") (pin "A") (pinfunction "A_A") (pintype "passive"))
      (node (ref "R41") (pin "1") (pinfunction "1_1") (pintype "passive"))
    )
    (net (code "40") (name "Net-(DOT4-PadA)") (class "Default")
      (node (ref "DOT4") (pin "A") (pinfunction "A_A") (pintype "passive"))
      (node (ref "R42") (pin "1") (pinfunction "1_1") (pintype "passive"))
    )
    (net (code "41") (name "Net-(E1-PadA)") (class "Default")
      (node (ref "E1") (pin "A") (pinfunction "A_A") (pintype "passive"))
      (node (ref "R23") (pin "1") (pinfunction "1_1") (pintype "passive"))
    )
    (net (code "42") (name "Net-(E2-PadA)") (class "Default")
      (node (ref "E2") (pin "A") (pinfunction "A_A") (pintype "passive"))
      (node (ref "R24") (pin "1") (pinfunction "1_1") (pintype "passive"))
    )
    (net (code "43") (name "Net-(E3-PadA)") (class "Default")
      (node (ref "E3") (pin "A") (pinfunction "A_A") (pintype "passive"))
      (node (ref "R25") (pin "1") (pinfunction "1_1") (pintype "passive"))
    )
    (net (code "44") (name "Net-(E4-PadA)") (class "Default")
      (node (ref "E4") (pin "A") (pinfunction "A_A") (pintype "passive"))
      (node (ref "R26") (pin "1") (pinfunction "1_1") (pintype "passive"))
    )
    (net (code "45") (name "Net-(E5-PadA)") (class "Default")
      (node (ref "E5") (pin "A") (pinfunction "A_A") (pintype "passive"))
      (node (ref "R27") (pin "1") (pinfunction "1_1") (pintype "passive"))
    )
    (net (code "46") (name "Net-(F1-PadA)") (class "Default")
      (node (ref "F1") (pin "A") (pinfunction "A_A") (pintype "passive"))
      (node (ref "R28") (pin "1") (pinfunction "1_1") (pintype "passive"))
    )
    (net (code "47") (name "Net-(F2-PadA)") (class "Default")
      (node (ref "F2") (pin "A") (pinfunction "A_A") (pintype "passive"))
      (node (ref "R29") (pin "1") (pinfunction "1_1") (pintype "passive"))
    )
    (net (code "48") (name "Net-(F3-PadA)") (class "Default")
      (node (ref "F3") (pin "A") (pinfunction "A_A") (pintype "passive"))
      (node (ref "R30") (pin "1") (pinfunction "1_1") (pintype "passive"))
    )
    (net (code "49") (name "Net-(F4-PadA)") (class "Default")
      (node (ref "F4") (pin "A") (pinfunction "A_A") (pintype "passive"))
      (node (ref "R31") (pin "1") (pinfunction "1_1") (pintype "passive"))
    )
    (net (code "50") (name "Net-(F5-PadA)") (class "Default")
      (node (ref "F5") (pin "A") (pinfunction "A_A") (pintype "passive"))
      (node (ref "R32") (pin "1") (pinfunction "1_1") (pintype "passive"))
    )
    (net (code "51") (name "Net-(G1-PadA)") (class "Default")
      (node (ref "G1") (pin "A") (pinfunction "A_A") (pintype "passive"))
      (node (ref "R33") (pin "1") (pinfunction "1_1") (pintype "passive"))
    )
    (net (code "52") (name "Net-(G2-PadA)") (class "Default")
      (node (ref "G2") (pin "A") (pinfunction "A_A") (pintype "passive"))
      (node (ref "R34") (pin "1") (pinfunction "1_1") (pintype "passive"))
    )
    (net (code "53") (name "Net-(G3-PadA)") (class "Default")
      (node (ref "G3") (pin "A") (pinfunction "A_A") (pintype "passive"))
      (node (ref "R35") (pin "1") (pinfunction "1_1") (pintype "passive"))
    )
    (net (code "54") (name "Net-(G4-PadA)") (class "Default")
      (node (ref "G4") (pin "A") (pinfunction "A_A") (pintype "passive"))
      (node (ref "R36") (pin "1") (pinfunction "1_1") (pintype "passive"))
    )
    (net (code "55") (name "Net-(G5-PadA)") (class "Default")
      (node (ref "G5") (pin "A") (pinfunction "A_A") (pintype "passive"))
      (node (ref "R37") (pin "1") (pinfunction "1_1") (pintype "passive"))
    )
    (net (code "56") (name "Net-(G6-PadA)") (class "Default")
      (node (ref "G6") (pin "A") (pinfunction "A_A") (pintype "passive"))
      (node (ref "R38") (pin "1") (pinfunction "1_1") (pintype "passive"))
    )
    (net (code "57") (name "Net-(LED1-C)") (class "Default")
      (node (ref "LED1") (pin "K") (pinfunction "C_K") (pintype "passive"))
      (node (ref "LED2") (pin "K") (pinfunction "C_K") (pintype "passive"))
      (node (ref "Q19") (pin "3") (pinfunction "D_3") (pintype "bidirectional"))
    )
    (net (code "58") (name "Net-(LED1-PadA)") (class "Default")
      (node (ref "LED1") (pin "A") (pinfunction "A_A") (pintype "passive"))
      (node (ref "R71") (pin "1") (pinfunction "1_1") (pintype "passive"))
    )
    (net (code "59") (name "Net-(LED2-PadA)") (class "Default")
      (node (ref "LED2") (pin "A") (pinfunction "A_A") (pintype "passive"))
      (node (ref "R72") (pin "1") (pinfunction "1_1") (pintype "passive"))
    )
    (net (code "60") (name "Net-(Q1-D)") (class "Default")
      (node (ref "Q1") (pin "3") (pinfunction "D_3") (pintype "bidirectional"))
      (node (ref "R45") (pin "1") (pinfunction "1_1") (pintype "passive"))
    )
    (net (code "61") (name "Net-(Q2-D)") (class "Default")
      (node (ref "Q2") (pin "3") (pinfunction "D_3") (pintype "bidirectional"))
      (node (ref "R1") (pin "2") (pinfunction "2_2") (pintype "passive"))
      (node (ref "R2") (pin "2") (pinfunction "2_2") (pintype "passive"))
      (node (ref "R3") (pin "2") (pinfunction "2_2") (pintype "passive"))
      (node (ref "R4") (pin "2") (pinfunction "2_2") (pintype "passive"))
      (node (ref "R5") (pin "2") (pinfunction "2_2") (pintype "passive"))
      (node (ref "R6") (pin "2") (pinfunction "2_2") (pintype "passive"))
    )
    (net (code "62") (name "Net-(Q2-G)") (class "Default")
      (node (ref "Q2") (pin "1") (pinfunction "G_1") (pintype "bidirectional"))
      (node (ref "R44") (pin "1") (pinfunction "1_1") (pintype "passive"))
      (node (ref "R45") (pin "2") (pinfunction "2_2") (pintype "passive"))
    )
    (net (code "63") (name "Net-(Q3-D)") (class "Default")
      (node (ref "JP2") (pin "2") (pinfunction "2_2") (pintype "passive"))
      (node (ref "Q3") (pin "3") (pinfunction "D_3") (pintype "bidirectional"))
      (node (ref "Q4") (pin "1") (pinfunction "G_1") (pintype "bidirectional"))
      (node (ref "R48") (pin "2") (pinfunction "2_2") (pintype "passive"))
    )
    (net (code "64") (name "Net-(Q3-G)") (class "Default")
      (node (ref "Q3") (pin "1") (pinfunction "G_1") (pintype "bidirectional"))
      (node (ref "R46") (pin "1") (pinfunction "1_1") (pintype "passive"))
      (node (ref "R47") (pin "1") (pinfunction "1_1") (pintype "passive"))
    )
    (net (code "65") (name "Net-(Q3-S)") (class "Default")
      (node (ref "JP1") (pin "1") (pinfunction "1_1") (pintype "passive"))
      (node (ref "Q3") (pin "2") (pinfunction "S_2") (pintype "bidirectional"))
      (node (ref "R47") (pin "2") (pinfunction "2_2") (pintype "passive"))
    )
    (net (code "66") (name "Net-(Q5-D)") (class "Default")
      (node (ref "Q5") (pin "3") (pinfunction "D_3") (pintype "bidirectional"))
      (node (ref "R10") (pin "2") (pinfunction "2_2") (pintype "passive"))
      (node (ref "R11") (pin "2") (pinfunction "2_2") (pintype "passive"))
      (node (ref "R7") (pin "2") (pinfunction "2_2") (pintype "passive"))
      (node (ref "R8") (pin "2") (pinfunction "2_2") (pintype "passive"))
      (node (ref "R9") (pin "2") (pinfunction "2_2") (pintype "passive"))
    )
    (net (code "67") (name "Net-(Q5-G)") (class "Default")
      (node (ref "Q5") (pin "1") (pinfunction "G_1") (pintype "bidirectional"))
      (node (ref "R49") (pin "1") (pinfunction "1_1") (pintype "passive"))
      (node (ref "R50") (pin "2") (pinfunction "2_2") (pintype "passive"))
    )
    (net (code "68") (name "Net-(Q6-D)") (class "Default")
      (node (ref "Q6") (pin "3") (pinfunction "D_3") (pintype "bidirectional"))
      (node (ref "R50") (pin "1") (pinfunction "1_1") (pintype "passive"))
    )
    (net (code "69") (name "Net-(Q7-D)") (class "Default")
      (node (ref "Q7") (pin "3") (pinfunction "D_3") (pintype "bidirectional"))
      (node (ref "R12") (pin "2") (pinfunction "2_2") (pintype "passive"))
      (node (ref "R13") (pin "2") (pinfunction "2_2") (pintype "passive"))
      (node (ref "R14") (pin "2") (pinfunction "2_2") (pintype "passive"))
      (node (ref "R15") (pin "2") (pinfunction "2_2") (pintype "passive"))
      (node (ref "R16") (pin "2") (pinfunction "2_2") (pintype "passive"))
    )
    (net (code "70") (name "Net-(Q7-G)") (class "Default")
      (node (ref "Q7") (pin "1") (pinfunction "G_1") (pintype "bidirectional"))
      (node (ref "R52") (pin "1") (pinfunction "1_1") (pintype "passive"))
      (node (ref "R53") (pin "2") (pinfunction "2_2") (pintype "passive"))
    )
    (net (code "71") (name "Net-(Q8-D)") (class "Default")
      (node (ref "Q8") (pin "3") (pinfunction "D_3") (pintype "bidirectional"))
      (node (ref "R53") (pin "1") (pinfunction "1_1") (pintype "passive"))
    )
    (net (code "72") (name "Net-(Q9-D)") (class "Default")
      (node (ref "Q9") (pin "3") (pinfunction "D_3") (pintype "bidirectional"))
      (node (ref "R17") (pin "2") (pinfunction "2_2") (pintype "passive"))
      (node (ref "R18") (pin "2") (pinfunction "2_2") (pintype "passive"))
      (node (ref "R19") (pin "2") (pinfunction "2_2") (pintype "passive"))
      (node (ref "R20") (pin "2") (pinfunction "2_2") (pintype "passive"))
      (node (ref "R21") (pin "2") (pinfunction "2_2") (pintype "passive"))
      (node (ref "R22") (pin "2") (pinfunction "2_2") (pintype "passive"))
    )
    (net (code "73") (name "Net-(Q9-G)") (class "Default")
      (node (ref "Q9") (pin "1") (pinfunction "G_1") (pintype "bidirectional"))
      (node (ref "R55") (pin "1") (pinfunction "1_1") (pintype "passive"))
      (node (ref "R56") (pin "2") (pinfunction "2_2") (pintype "passive"))
    )
    (net (code "74") (name "Net-(Q10-D)") (class "Default")
      (node (ref "Q10") (pin "3") (pinfunction "D_3") (pintype "bidirectional"))
      (node (ref "R56") (pin "1") (pinfunction "1_1") (pintype "passive"))
    )
    (net (code "75") (name "Net-(Q11-D)") (class "Default")
      (node (ref "Q11") (pin "3") (pinfunction "D_3") (pintype "bidirectional"))
      (node (ref "R23") (pin "2") (pinfunction "2_2") (pintype "passive"))
      (node (ref "R24") (pin "2") (pinfunction "2_2") (pintype "passive"))
      (node (ref "R25") (pin "2") (pinfunction "2_2") (pintype "passive"))
      (node (ref "R26") (pin "2") (pinfunction "2_2") (pintype "passive"))
      (node (ref "R27") (pin "2") (pinfunction "2_2") (pintype "passive"))
    )
    (net (code "76") (name "Net-(Q11-G)") (class "Default")
      (node (ref "Q11") (pin "1") (pinfunction "G_1") (pintype "bidirectional"))
      (node (ref "R58") (pin "1") (pinfunction "1_1") (pintype "passive"))
      (node (ref "R59") (pin "2") (pinfunction "2_2") (pintype "passive"))
    )
    (net (code "77") (name "Net-(Q12-D)") (class "Default")
      (node (ref "Q12") (pin "3") (pinfunction "D_3") (pintype "bidirectional"))
      (node (ref "R59") (pin "1") (pinfunction "1_1") (pintype "passive"))
    )
    (net (code "78") (name "Net-(Q13-D)") (class "Default")
      (node (ref "Q13") (pin "3") (pinfunction "D_3") (pintype "bidirectional"))
      (node (ref "R28") (pin "2") (pinfunction "2_2") (pintype "passive"))
      (node (ref "R29") (pin "2") (pinfunction "2_2") (pintype "passive"))
      (node (ref "R30") (pin "2") (pinfunction "2_2") (pintype "passive"))
      (node (ref "R31") (pin "2") (pinfunction "2_2") (pintype "passive"))
      (node (ref "R32") (pin "2") (pinfunction "2_2") (pintype "passive"))
    )
    (net (code "79") (name "Net-(Q13-G)") (class "Default")
      (node (ref "Q13") (pin "1") (pinfunction "G_1") (pintype "bidirectional"))
      (node (ref "R61") (pin "1") (pinfunction "1_1") (pintype "passive"))
      (node (ref "R62") (pin "2") (pinfunction "2_2") (pintype "passive"))
    )
    (net (code "80") (name "Net-(Q14-D)") (class "Default")
      (node (ref "Q14") (pin "3") (pinfunction "D_3") (pintype "bidirectional"))
      (node (ref "R62") (pin "1") (pinfunction "1_1") (pintype "passive"))
    )
    (net (code "81") (name "Net-(Q15-D)") (class "Default")
      (node (ref "Q15") (pin "3") (pinfunction "D_3") (pintype "bidirectional"))
      (node (ref "R33") (pin "2") (pinfunction "2_2") (pintype "passive"))
      (node (ref "R34") (pin "2") (pinfunction "2_2") (pintype "passive"))
      (node (ref "R35") (pin "2") (pinfunction "2_2") (pintype "passive"))
      (node (ref "R36") (pin "2") (pinfunction "2_2") (pintype "passive"))
      (node (ref "R37") (pin "2") (pinfunction "2_2") (pintype "passive"))
      (node (ref "R38") (pin "2") (pinfunction "2_2") (pintype "passive"))
    )
    (net (code "82") (name "Net-(Q15-G)") (class "Default")
      (node (ref "Q15") (pin "1") (pinfunction "G_1") (pintype "bidirectional"))
      (node (ref "R64") (pin "1") (pinfunction "1_1") (pintype "passive"))
      (node (ref "R65") (pin "2") (pinfunction "2_2") (pintype "passive"))
    )
    (net (code "83") (name "Net-(Q16-D)") (class "Default")
      (node (ref "Q16") (pin "3") (pinfunction "D_3") (pintype "bidirectional"))
      (node (ref "R65") (pin "1") (pinfunction "1_1") (pintype "passive"))
    )
    (net (code "84") (name "Net-(Q17-D)") (class "Default")
      (node (ref "Q17") (pin "3") (pinfunction "D_3") (pintype "bidirectional"))
      (node (ref "R39") (pin "2") (pinfunction "2_2") (pintype "passive"))
      (node (ref "R40") (pin "2") (pinfunction "2_2") (pintype "passive"))
      (node (ref "R41") (pin "2") (pinfunction "2_2") (pintype "passive"))
      (node (ref "R42") (pin "2") (pinfunction "2_2") (pintype "passive"))
    )
    (net (code "85") (name "Net-(Q17-G)") (class "Default")
      (node (ref "Q17") (pin "1") (pinfunction "G_1") (pintype "bidirectional"))
      (node (ref "R67") (pin "1") (pinfunction "1_1") (pintype "passive"))
      (node (ref "R68") (pin "2") (pinfunction "2_2") (pintype "passive"))
    )
    (net (code "86") (name "Net-(Q18-D)") (class "Default")
      (node (ref "Q18") (pin "3") (pinfunction "D_3") (pintype "bidirectional"))
      (node (ref "R68") (pin "1") (pinfunction "1_1") (pintype "passive"))
    )
    (net (code "87") (name "SEC") (class "Default")
      (node (ref "Q19") (pin "1") (pinfunction "G_1") (pintype "bidirectional"))
      (node (ref "R70") (pin "2") (pinfunction "2_2") (pintype "passive"))
      (node (ref "SEC") (pin "1") (pinfunction "1_1") (pintype "passive"))
    )
    (net (code "88") (name "VCC") (class "Default")
      (node (ref "JP1") (pin "2") (pinfunction "2_2") (pintype "passive"))
      (node (ref "ON") (pin "3") (pinfunction "S_3") (pintype "passive"))
      (node (ref "Q11") (pin "2") (pinfunction "S_2") (pintype "bidirectional"))
      (node (ref "Q13") (pin "2") (pinfunction "S_2") (pintype "bidirectional"))
      (node (ref "Q15") (pin "2") (pinfunction "S_2") (pintype "bidirectional"))
      (node (ref "Q17") (pin "2") (pinfunction "S_2") (pintype "bidirectional"))
      (node (ref "Q2") (pin "2") (pinfunction "S_2") (pintype "bidirectional"))
      (node (ref "Q5") (pin "2") (pinfunction "S_2") (pintype "bidirectional"))
      (node (ref "Q7") (pin "2") (pinfunction "S_2") (pintype "bidirectional"))
      (node (ref "Q9") (pin "2") (pinfunction "S_2") (pintype "bidirectional"))
      (node (ref "R44") (pin "2") (pinfunction "2_2") (pintype "passive"))
      (node (ref "R49") (pin "2") (pinfunction "2_2") (pintype "passive"))
      (node (ref "R52") (pin "2") (pinfunction "2_2") (pintype "passive"))
      (node (ref "R55") (pin "2") (pinfunction "2_2") (pintype "passive"))
      (node (ref "R58") (pin "2") (pinfunction "2_2") (pintype "passive"))
      (node (ref "R61") (pin "2") (pinfunction "2_2") (pintype "passive"))
      (node (ref "R64") (pin "2") (pinfunction "2_2") (pintype "passive"))
      (node (ref "R67") (pin "2") (pinfunction "2_2") (pintype "passive"))
    )
  )
)
